# Qwiic_GPS_-_Titan_X1.net
KiCad netlist of a schematic drawn in EAGLE
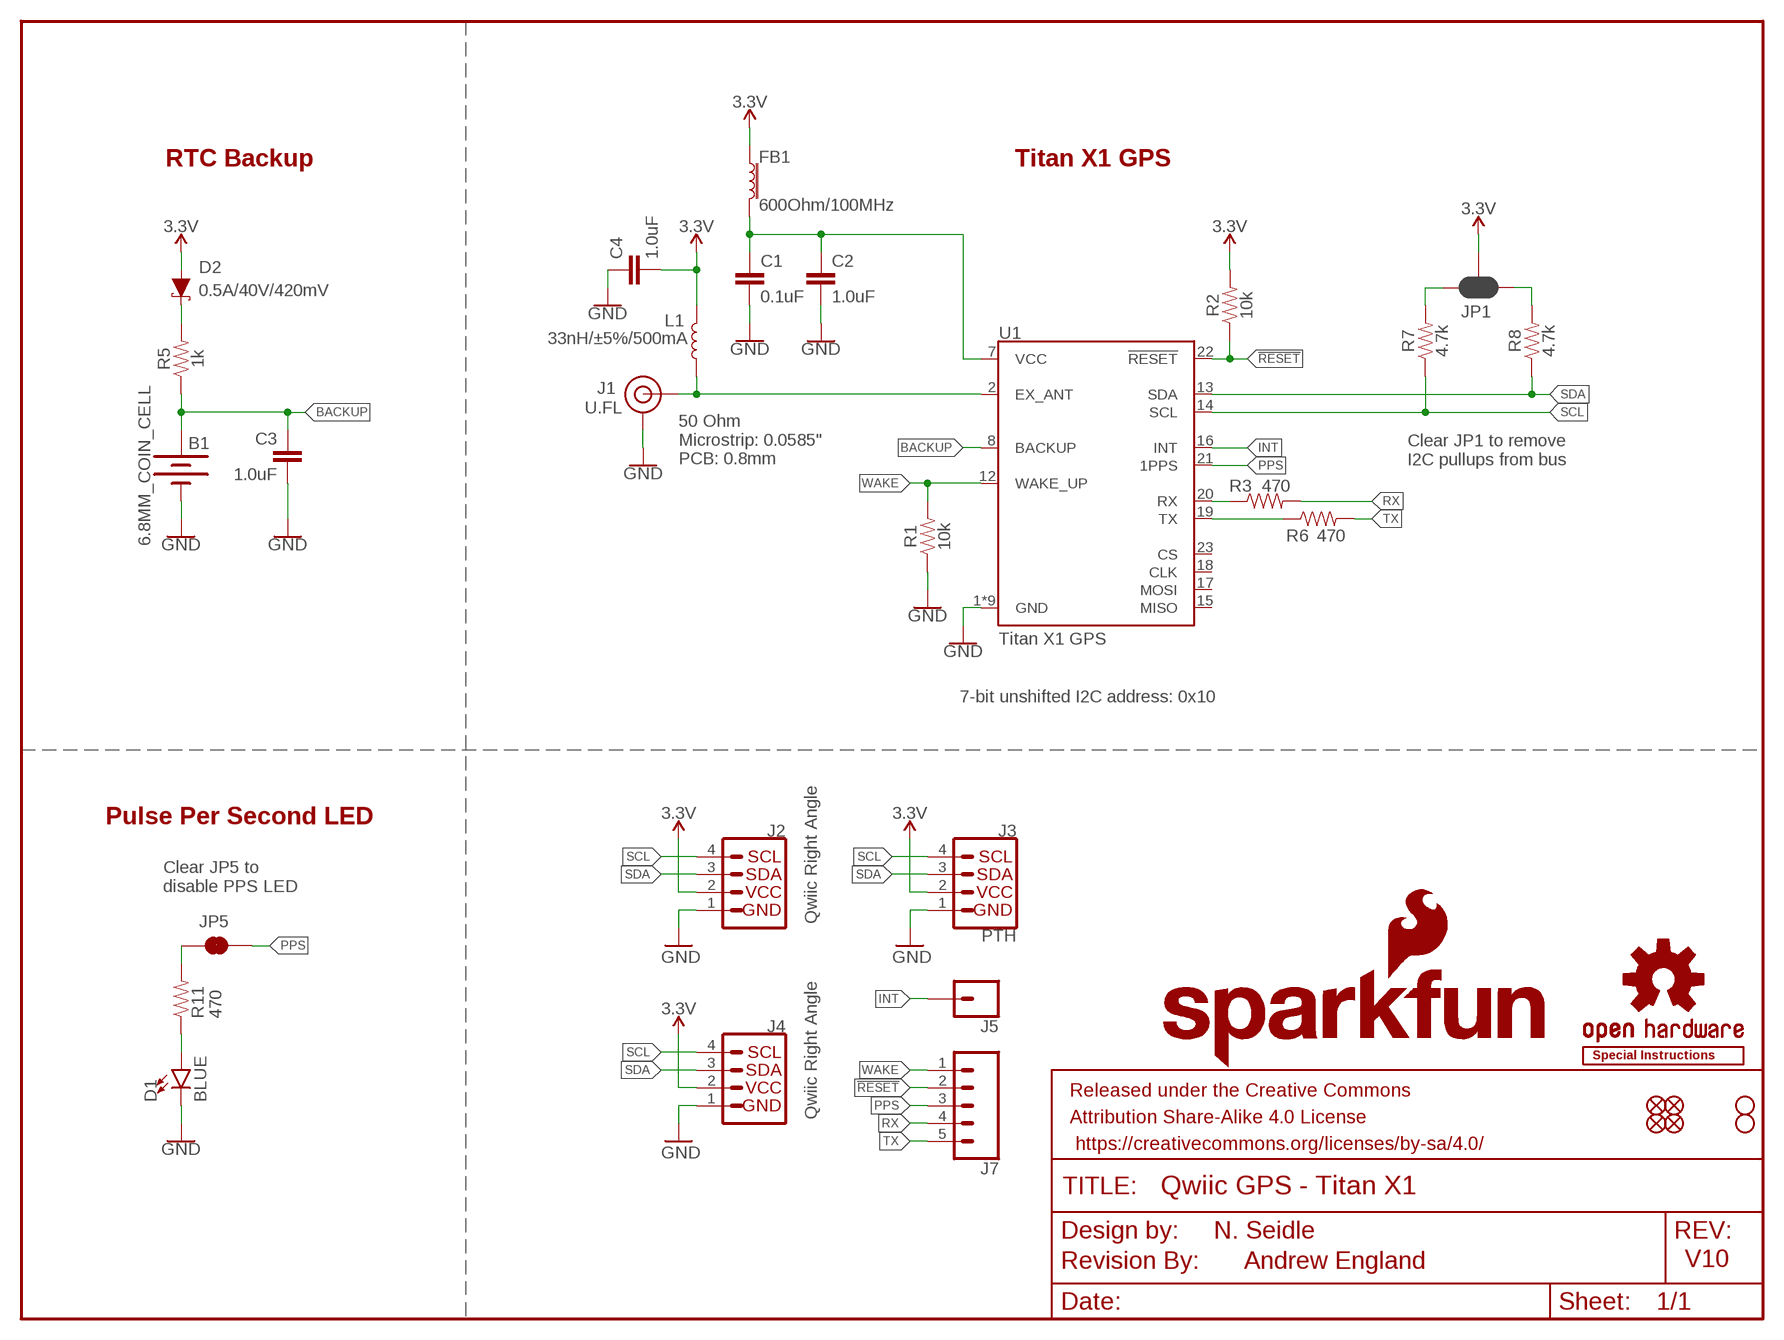
[diagram p0: schematic, sheet 1]

(export (version "E")
  (design (tool "Eeschema 10.0.6"))
  (components
    (comp (ref "B1")
      (value "6.8MM_COIN_CELL")
      (footprint "eagle-import:BATTCON-6.8MM")
      (libsource (lib "eagle-import") (part "BATTERY-6.8MM_SMD"))
    )
    (comp (ref "C1")
      (value "0.1uF")
      (footprint "eagle-import:0603")
      (libsource (lib "eagle-import") (part "0.1UF-0603-25V-(+80/-20%)"))
    )
    (comp (ref "C2")
      (value "1.0uF")
      (footprint "eagle-import:0603")
      (libsource (lib "eagle-import") (part "1.0UF-0603-16V-10%"))
    )
    (comp (ref "C3")
      (value "1.0uF")
      (footprint "eagle-import:0603")
      (libsource (lib "eagle-import") (part "1.0UF-0603-16V-10%"))
    )
    (comp (ref "C4")
      (value "1.0uF")
      (footprint "eagle-import:0603")
      (libsource (lib "eagle-import") (part "1.0UF-0603-16V-10%"))
    )
    (comp (ref "D1")
      (value "BLUE")
      (footprint "eagle-import:LED-0603")
      (libsource (lib "eagle-import") (part "LED-BLUE0603"))
    )
    (comp (ref "D2")
      (value "0.5A/40V/420mV")
      (footprint "eagle-import:SOD-323")
      (libsource (lib "eagle-import") (part "DIODE-SCHOTTKY-PMEG4005EJ"))
    )
    (comp (ref "FB1")
      (value "600Ohm/100MHz")
      (footprint "eagle-import:0603")
      (libsource (lib "eagle-import") (part "FERRITE_BEAD-0603"))
    )
    (comp (ref "FRAME1")
      (value "FRAME-LETTER")
      (footprint "eagle-import:CREATIVE_COMMONS")
      (libsource (lib "eagle-import") (part "FRAME-LETTER"))
    )
    (comp (ref "J1")
      (value "U.FL")
      (footprint "eagle-import:U.FL")
      (libsource (lib "eagle-import") (part "U.FL2PIN"))
    )
    (comp (ref "J2")
      (value "Qwiic Right Angle")
      (footprint "eagle-import:1X04_1MM_RA")
      (libsource (lib "eagle-import") (part "I2C_STANDARDQWIIC"))
    )
    (comp (ref "J3")
      (value "PTH")
      (footprint "eagle-import:1X04_NO_SILK")
      (libsource (lib "eagle-import") (part "SparkX_I2C_STANDARD_NO_SILK"))
    )
    (comp (ref "J4")
      (value "Qwiic Right Angle")
      (footprint "eagle-import:1X04_1MM_RA")
      (libsource (lib "eagle-import") (part "I2C_STANDARDQWIIC"))
    )
    (comp (ref "J5")
      (value "CONN_01PTH_NO_SILK_YES_STOP")
      (footprint "eagle-import:1X01_NO_SILK")
      (libsource (lib "eagle-import") (part "CONN_01PTH_NO_SILK_YES_STOP"))
    )
    (comp (ref "J7")
      (value "CONN_05NO_SILK")
      (footprint "eagle-import:1X05_NO_SILK")
      (libsource (lib "eagle-import") (part "CONN_05NO_SILK"))
    )
    (comp (ref "JP1")
      (value "JUMPER-SMT_3_2-NC_PASTE_SILK")
      (footprint "eagle-import:SMT-JUMPER_3_2-NC_PASTE_SILK")
      (libsource (lib "eagle-import") (part "JUMPER-SMT_3_2-NC_PASTE_SILK"))
    )
    (comp (ref "JP2")
      (value "FIDUCIALUFIDUCIAL")
      (footprint "eagle-import:MICRO-FIDUCIAL")
      (libsource (lib "eagle-import") (part "FIDUCIALUFIDUCIAL"))
    )
    (comp (ref "JP3")
      (value "STAND-OFF")
      (footprint "eagle-import:STAND-OFF")
      (libsource (lib "eagle-import") (part "STAND-OFF"))
    )
    (comp (ref "JP4")
      (value "STAND-OFF")
      (footprint "eagle-import:STAND-OFF")
      (libsource (lib "eagle-import") (part "STAND-OFF"))
    )
    (comp (ref "JP5")
      (value "JUMPER-SMT_2_NC_TRACE_NO-SILK")
      (footprint "eagle-import:SMT-JUMPER_2_NC_TRACE_NO-SILK")
      (libsource (lib "eagle-import") (part "JUMPER-SMT_2_NC_TRACE_NO-SILK"))
    )
    (comp (ref "JP6")
      (value "FIDUCIALUFIDUCIAL")
      (footprint "eagle-import:MICRO-FIDUCIAL")
      (libsource (lib "eagle-import") (part "FIDUCIALUFIDUCIAL"))
    )
    (comp (ref "JP7")
      (value "FIDUCIALUFIDUCIAL")
      (footprint "eagle-import:MICRO-FIDUCIAL")
      (libsource (lib "eagle-import") (part "FIDUCIALUFIDUCIAL"))
    )
    (comp (ref "JP8")
      (value "FIDUCIALUFIDUCIAL")
      (footprint "eagle-import:MICRO-FIDUCIAL")
      (libsource (lib "eagle-import") (part "FIDUCIALUFIDUCIAL"))
    )
    (comp (ref "L1")
      (value "33nH/±5%/500mA")
      (footprint "eagle-import:0603")
      (libsource (lib "eagle-import") (part "INDUCTOR-0603-33NH"))
    )
    (comp (ref "LOGO1")
      (value "OSHW-LOGOMINI")
      (footprint "eagle-import:OSHW-LOGO-MINI")
      (libsource (lib "eagle-import") (part "OSHW-LOGOMINI"))
    )
    (comp (ref "LOGO2")
      (value "SFE_LOGO_NAME_FLAME.1_INCH")
      (footprint "eagle-import:SFE_LOGO_NAME_FLAME_.1")
      (libsource (lib "eagle-import") (part "SFE_LOGO_NAME_FLAME.1_INCH"))
    )
    (comp (ref "LOGO3")
      (value "REVISION")
      (footprint "eagle-import:REVISION")
      (libsource (lib "eagle-import") (part "REVISION"))
    )
    (comp (ref "R1")
      (value "10k")
      (footprint "eagle-import:0603")
      (libsource (lib "eagle-import") (part "10KOHM-0603-1/10W-1%"))
    )
    (comp (ref "R2")
      (value "10k")
      (footprint "eagle-import:0603")
      (libsource (lib "eagle-import") (part "10KOHM-0603-1/10W-1%"))
    )
    (comp (ref "R3")
      (value "470")
      (footprint "eagle-import:0603")
      (libsource (lib "eagle-import") (part "470OHM-0603-1/10W-1%"))
    )
    (comp (ref "R5")
      (value "1k")
      (footprint "eagle-import:0603")
      (libsource (lib "eagle-import") (part "1KOHM-0603-1/10W-1%"))
    )
    (comp (ref "R6")
      (value "470")
      (footprint "eagle-import:0603")
      (libsource (lib "eagle-import") (part "470OHM-0603-1/10W-1%"))
    )
    (comp (ref "R7")
      (value "4.7k")
      (footprint "eagle-import:0603")
      (libsource (lib "eagle-import") (part "4.7KOHM-0603-1/10W-1%"))
    )
    (comp (ref "R8")
      (value "4.7k")
      (footprint "eagle-import:0603")
      (libsource (lib "eagle-import") (part "4.7KOHM-0603-1/10W-1%"))
    )
    (comp (ref "R11")
      (value "470")
      (footprint "eagle-import:0603")
      (libsource (lib "eagle-import") (part "470OHM-0603-1/10W-1%"))
    )
    (comp (ref "U$3")
      (value "SPECIAL_INSTRUCTIONS-PRODUCTION")
      (footprint "eagle-import:PRODUCTION_INSTRUCTIONS")
      (libsource (lib "eagle-import") (part "SPECIAL_INSTRUCTIONS-PRODUCTION"))
    )
    (comp (ref "U1")
      (value "Titan X1 GPS")
      (footprint "eagle-import:TITAN_X1_GPS")
      (libsource (lib "eagle-import") (part "TITAN_X1_GPS"))
    )
  )
  (nets
    (net (code "1") (name "/~{RESET}") (class "Default")
      (node (ref "J7") (pin "2") (pinfunction "2_2") (pintype "passive"))
      (node (ref "R2") (pin "1") (pinfunction "1_1") (pintype "passive"))
      (node (ref "U1") (pin "22") (pinfunction "~{RESET}_22") (pintype "bidirectional"))
    )
    (net (code "2") (name "3.3V") (class "Default")
      (node (ref "C4") (pin "2") (pinfunction "2_2") (pintype "passive"))
      (node (ref "D2") (pin "A") (pinfunction "A_A") (pintype "passive"))
      (node (ref "FB1") (pin "1") (pinfunction "1_1") (pintype "passive"))
      (node (ref "J2") (pin "2") (pinfunction "2_2") (pintype "power_in"))
      (node (ref "J3") (pin "2") (pinfunction "VCC_2") (pintype "power_in"))
      (node (ref "J4") (pin "2") (pinfunction "2_2") (pintype "power_in"))
      (node (ref "JP1") (pin "2") (pinfunction "2_2") (pintype "passive"))
      (node (ref "L1") (pin "2") (pinfunction "2_2") (pintype "passive"))
      (node (ref "R2") (pin "2") (pinfunction "2_2") (pintype "passive"))
    )
    (net (code "3") (name "BACKUP") (class "Default")
      (node (ref "B1") (pin "+") (pinfunction "+_+") (pintype "power_in"))
      (node (ref "C3") (pin "1") (pinfunction "1_1") (pintype "passive"))
      (node (ref "R5") (pin "1") (pinfunction "1_1") (pintype "passive"))
      (node (ref "U1") (pin "8") (pinfunction "BACKUP_8") (pintype "bidirectional"))
    )
    (net (code "4") (name "GND") (class "Default")
      (node (ref "B1") (pin "-") (pinfunction "-_-") (pintype "power_in"))
      (node (ref "C1") (pin "2") (pinfunction "2_2") (pintype "passive"))
      (node (ref "C2") (pin "2") (pinfunction "2_2") (pintype "passive"))
      (node (ref "C3") (pin "2") (pinfunction "2_2") (pintype "passive"))
      (node (ref "C4") (pin "1") (pinfunction "1_1") (pintype "passive"))
      (node (ref "D1") (pin "C") (pinfunction "C_C") (pintype "passive"))
      (node (ref "J1") (pin "1") (pinfunction "GND_1") (pintype "bidirectional"))
      (node (ref "J1") (pin "2") (pinfunction "GND_2") (pintype "bidirectional"))
      (node (ref "J2") (pin "1") (pinfunction "1_1") (pintype "power_in"))
      (node (ref "J3") (pin "1") (pinfunction "GND_1") (pintype "power_in"))
      (node (ref "J4") (pin "1") (pinfunction "1_1") (pintype "power_in"))
      (node (ref "R1") (pin "1") (pinfunction "1_1") (pintype "passive"))
      (node (ref "U1") (pin "1") (pinfunction "GND_1") (pintype "bidirectional"))
      (node (ref "U1") (pin "10") (pinfunction "GND_10") (pintype "bidirectional"))
      (node (ref "U1") (pin "11") (pinfunction "GND_11") (pintype "bidirectional"))
      (node (ref "U1") (pin "24") (pinfunction "GND_24") (pintype "bidirectional"))
      (node (ref "U1") (pin "3") (pinfunction "GND_3") (pintype "bidirectional"))
      (node (ref "U1") (pin "4") (pinfunction "GND_4") (pintype "bidirectional"))
      (node (ref "U1") (pin "5") (pinfunction "GND_5") (pintype "bidirectional"))
      (node (ref "U1") (pin "6") (pinfunction "GND_6") (pintype "bidirectional"))
      (node (ref "U1") (pin "9") (pinfunction "GND_9") (pintype "bidirectional"))
    )
    (net (code "5") (name "INT") (class "Default")
      (node (ref "J5") (pin "1") (pinfunction "1_1") (pintype "passive"))
      (node (ref "U1") (pin "16") (pinfunction "INT_16") (pintype "bidirectional"))
    )
    (net (code "6") (name "Net-(D1-PadA)") (class "Default")
      (node (ref "D1") (pin "A") (pinfunction "A_A") (pintype "passive"))
      (node (ref "R11") (pin "1") (pinfunction "1_1") (pintype "passive"))
    )
    (net (code "7") (name "Net-(D2-PadC)") (class "Default")
      (node (ref "D2") (pin "C") (pinfunction "C_C") (pintype "passive"))
      (node (ref "R5") (pin "2") (pinfunction "2_2") (pintype "passive"))
    )
    (net (code "8") (name "Net-(J1-SIGNAL)") (class "Default")
      (node (ref "J1") (pin "FEED") (pinfunction "SIGNAL_FEED") (pintype "bidirectional"))
      (node (ref "L1") (pin "1") (pinfunction "1_1") (pintype "passive"))
      (node (ref "U1") (pin "2") (pinfunction "EX_ANT_2") (pintype "bidirectional"))
    )
    (net (code "9") (name "Net-(JP1-Pad1)") (class "Default")
      (node (ref "JP1") (pin "1") (pinfunction "1_1") (pintype "passive"))
      (node (ref "R8") (pin "2") (pinfunction "2_2") (pintype "passive"))
    )
    (net (code "10") (name "Net-(JP1-Pad3)") (class "Default")
      (node (ref "JP1") (pin "3") (pinfunction "3_3") (pintype "passive"))
      (node (ref "R7") (pin "2") (pinfunction "2_2") (pintype "passive"))
    )
    (net (code "11") (name "Net-(JP5-Pad1)") (class "Default")
      (node (ref "JP5") (pin "1") (pinfunction "1_1") (pintype "passive"))
      (node (ref "R11") (pin "2") (pinfunction "2_2") (pintype "passive"))
    )
    (net (code "12") (name "Net-(U1-RX)") (class "Default")
      (node (ref "R3") (pin "1") (pinfunction "1_1") (pintype "passive"))
      (node (ref "U1") (pin "20") (pinfunction "RX_20") (pintype "bidirectional"))
    )
    (net (code "13") (name "Net-(U1-TX)") (class "Default")
      (node (ref "R6") (pin "1") (pinfunction "1_1") (pintype "passive"))
      (node (ref "U1") (pin "19") (pinfunction "TX_19") (pintype "bidirectional"))
    )
    (net (code "14") (name "Net-(U1-VCC)") (class "Default")
      (node (ref "C1") (pin "1") (pinfunction "1_1") (pintype "passive"))
      (node (ref "C2") (pin "1") (pinfunction "1_1") (pintype "passive"))
      (node (ref "FB1") (pin "2") (pinfunction "2_2") (pintype "passive"))
      (node (ref "U1") (pin "7") (pinfunction "VCC_7") (pintype "bidirectional"))
    )
    (net (code "15") (name "PPS") (class "Default")
      (node (ref "J7") (pin "3") (pinfunction "3_3") (pintype "passive"))
      (node (ref "JP5") (pin "2") (pinfunction "2_2") (pintype "passive"))
      (node (ref "U1") (pin "21") (pinfunction "1PPS_21") (pintype "bidirectional"))
    )
    (net (code "16") (name "RX") (class "Default")
      (node (ref "J7") (pin "4") (pinfunction "4_4") (pintype "passive"))
      (node (ref "R3") (pin "2") (pinfunction "2_2") (pintype "passive"))
    )
    (net (code "17") (name "SCL") (class "Default")
      (node (ref "J2") (pin "4") (pinfunction "4_4") (pintype "passive"))
      (node (ref "J3") (pin "4") (pinfunction "SCL_4") (pintype "passive"))
      (node (ref "J4") (pin "4") (pinfunction "4_4") (pintype "passive"))
      (node (ref "R7") (pin "1") (pinfunction "1_1") (pintype "passive"))
      (node (ref "U1") (pin "14") (pinfunction "SCL_14") (pintype "bidirectional"))
    )
    (net (code "18") (name "SDA") (class "Default")
      (node (ref "J2") (pin "3") (pinfunction "3_3") (pintype "passive"))
      (node (ref "J3") (pin "3") (pinfunction "SDA_3") (pintype "passive"))
      (node (ref "J4") (pin "3") (pinfunction "3_3") (pintype "passive"))
      (node (ref "R8") (pin "1") (pinfunction "1_1") (pintype "passive"))
      (node (ref "U1") (pin "13") (pinfunction "SDA_13") (pintype "bidirectional"))
    )
    (net (code "19") (name "TX") (class "Default")
      (node (ref "J7") (pin "5") (pinfunction "5_5") (pintype "passive"))
      (node (ref "R6") (pin "2") (pinfunction "2_2") (pintype "passive"))
    )
    (net (code "20") (name "WAKE") (class "Default")
      (node (ref "J7") (pin "1") (pinfunction "1_1") (pintype "passive"))
      (node (ref "R1") (pin "2") (pinfunction "2_2") (pintype "passive"))
      (node (ref "U1") (pin "12") (pinfunction "WAKE_UP_12") (pintype "bidirectional"))
    )
    (net (code "21") (name "unconnected-(U1-CLK-Pad18)") (class "Default")
      (node (ref "U1") (pin "18") (pinfunction "CLK_18") (pintype "bidirectional"))
    )
    (net (code "22") (name "unconnected-(U1-CS-Pad23)") (class "Default")
      (node (ref "U1") (pin "23") (pinfunction "CS_23") (pintype "bidirectional"))
    )
    (net (code "23") (name "unconnected-(U1-MISO-Pad15)") (class "Default")
      (node (ref "U1") (pin "15") (pinfunction "MISO_15") (pintype "bidirectional"))
    )
    (net (code "24") (name "unconnected-(U1-MOSI-Pad17)") (class "Default")
      (node (ref "U1") (pin "17") (pinfunction "MOSI_17") (pintype "bidirectional"))
    )
  )
)
